# MCU.net
KiCad netlist of a schematic drawn in Altium Designer
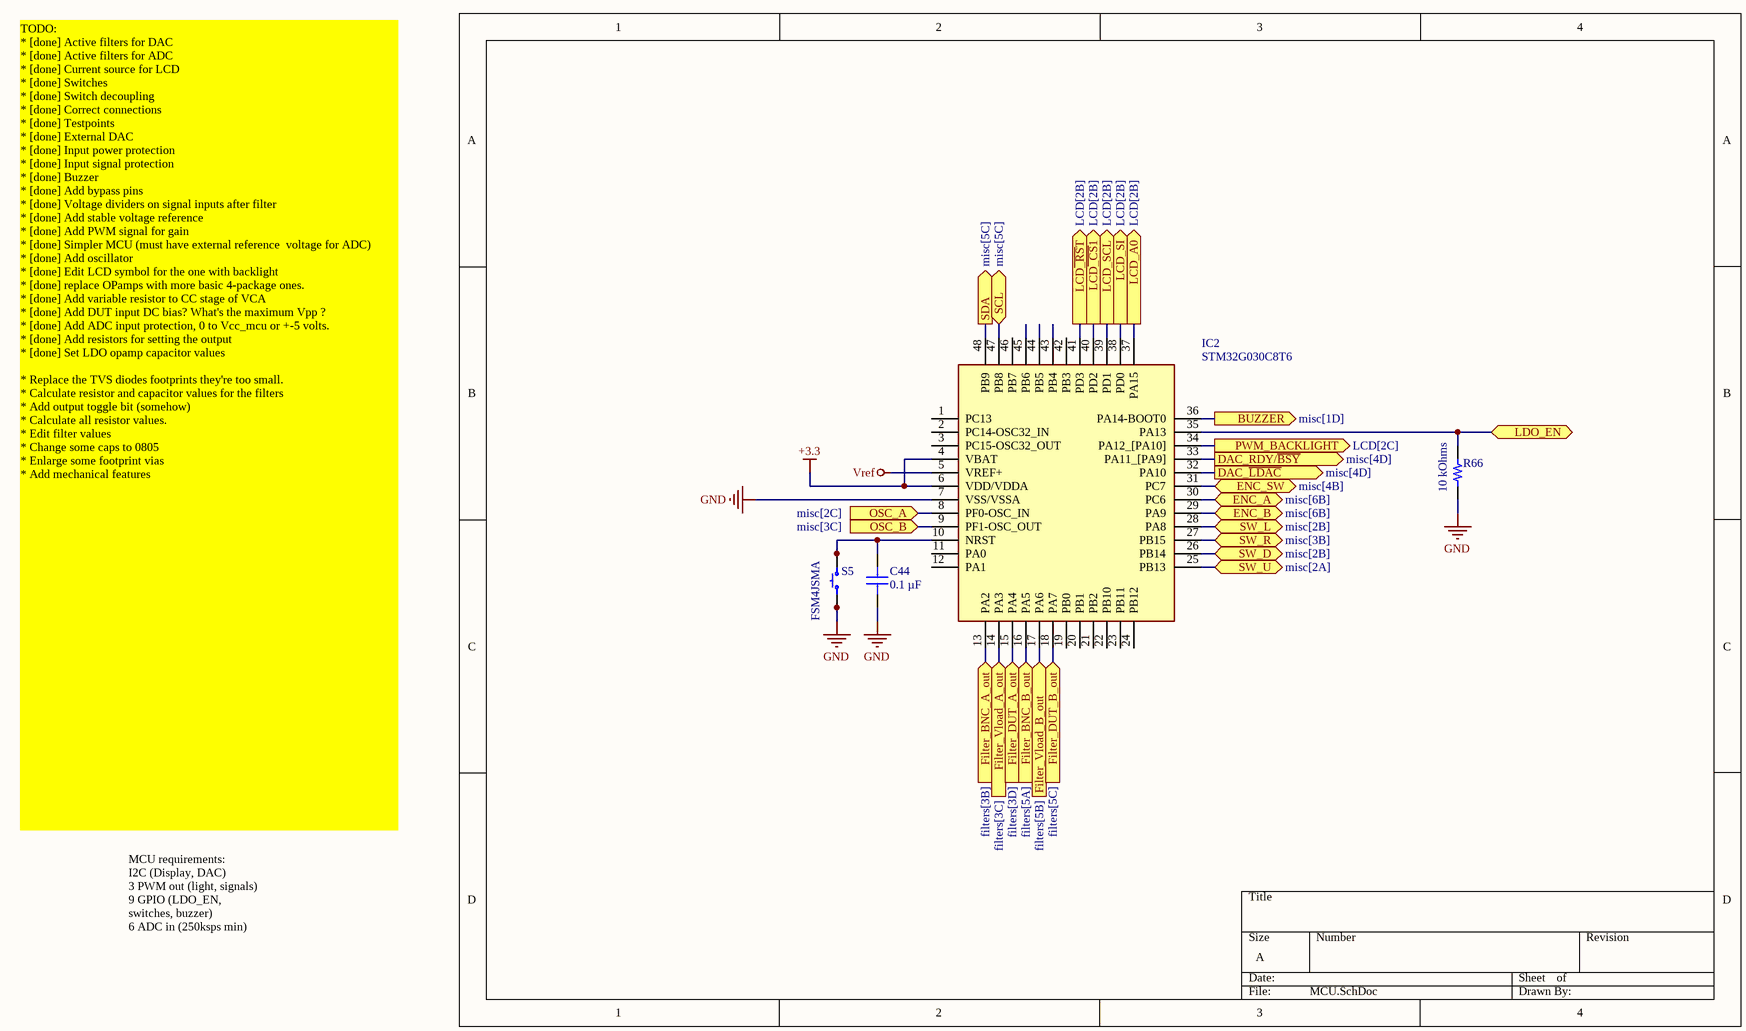
[diagram p0: MCU.SchDoc]

(export (version "E")
  (design (tool "Eeschema 10.0.6"))
  (components
    (comp (ref "C44")
      (value "0.1 µF")
      (footprint "CAP 1206_3216 - 0.8MM")
      (description "CAP CER 0.1UF 50V X7R 1206")
      (fields
        (field (name "PART NUMBER") "885012208087")
        (field (name "CAPACITANCE") "0.1 µF")
        (field (name "MANUFACTURER") "Würth Elektronik")
      )
      (libsource (lib "Celestial Altium Library - altium_library") (part "Capacitor"))
    )
    (comp (ref "IC2")
      (value "STM32G030C8T6")
      (footprint "QFP50P900X900X160-48N")
      (description "Integrated Circuit")
      (fields (field (name "MOUSER PART NUMBER") "511-STM32G030C8T6"))
      (libsource (lib "za_koncar") (part "STM32G030C8T6"))
    )
    (comp (ref "R66")
      (value "10 kOhms")
      (footprint "YAGEO RES 1206_3216")
      (description "RES SMD 10K OHM 1% 1/4W 1206")
      (fields (field (name "PART NUMBER") "RT1206FRE0710KL") (field (name "MANUFACTURER") "Yageo"))
      (libsource (lib "Celestial Altium Library - altium_library") (part "Resistor"))
    )
    (comp (ref "S5")
      (value "FSM4JSMA")
      (footprint "TE FSM4JSMA")
      (description "SWITCH TACTILE SPST-NO 0.05A 24V")
      (fields (field (name "MANUFACTURER") "TE Connectivity ALCOSWITCH Switches"))
      (libsource (lib "Celestial Altium Library - altium_library") (part "SPST-NO 4 PIN"))
    )
  )
  (nets
    (net (code "1") (name "+3.3") (class "Default")
      (node (ref "IC2") (pin "4") (pinfunction "VBAT_4") (pintype "passive"))
      (node (ref "IC2") (pin "6") (pinfunction "VDD/VDDA_6") (pintype "passive"))
    )
    (net (code "2") (name "/BUZZER") (class "Default")
      (node (ref "IC2") (pin "36") (pinfunction "PA14-BOOT0_36") (pintype "passive"))
    )
    (net (code "3") (name "/DAC_RDY{slash}~{BSY}") (class "Default")
      (node (ref "IC2") (pin "33") (pinfunction "PA11_[PA9]_33") (pintype "passive"))
    )
    (net (code "4") (name "/DAC_~{LDAC}") (class "Default")
      (node (ref "IC2") (pin "32") (pinfunction "PA10_32") (pintype "passive"))
    )
    (net (code "5") (name "/ENC_A") (class "Default")
      (node (ref "IC2") (pin "30") (pinfunction "PC6_30") (pintype "passive"))
    )
    (net (code "6") (name "/ENC_B") (class "Default")
      (node (ref "IC2") (pin "29") (pinfunction "PA9_29") (pintype "passive"))
    )
    (net (code "7") (name "/ENC_SW") (class "Default")
      (node (ref "IC2") (pin "31") (pinfunction "PC7_31") (pintype "passive"))
    )
    (net (code "8") (name "/Filter_BNC_A_out") (class "Default")
      (node (ref "IC2") (pin "13") (pinfunction "PA2_13") (pintype "passive"))
    )
    (net (code "9") (name "/Filter_BNC_B_out") (class "Default")
      (node (ref "IC2") (pin "16") (pinfunction "PA5_16") (pintype "passive"))
    )
    (net (code "10") (name "/Filter_DUT_A_out") (class "Default")
      (node (ref "IC2") (pin "15") (pinfunction "PA4_15") (pintype "passive"))
    )
    (net (code "11") (name "/Filter_DUT_B_out") (class "Default")
      (node (ref "IC2") (pin "18") (pinfunction "PA7_18") (pintype "passive"))
    )
    (net (code "12") (name "/Filter_Vload_A_out") (class "Default")
      (node (ref "IC2") (pin "14") (pinfunction "PA3_14") (pintype "passive"))
    )
    (net (code "13") (name "/Filter_Vload_B_out") (class "Default")
      (node (ref "IC2") (pin "17") (pinfunction "PA6_17") (pintype "passive"))
    )
    (net (code "14") (name "/LCD_A0") (class "Default")
      (node (ref "IC2") (pin "37") (pinfunction "PA15_37") (pintype "passive"))
    )
    (net (code "15") (name "/LCD_SCL") (class "Default")
      (node (ref "IC2") (pin "39") (pinfunction "PD1_39") (pintype "passive"))
    )
    (net (code "16") (name "/LCD_SI") (class "Default")
      (node (ref "IC2") (pin "38") (pinfunction "PD0_38") (pintype "passive"))
    )
    (net (code "17") (name "/LCD~{_CS}1") (class "Default")
      (node (ref "IC2") (pin "40") (pinfunction "PD2_40") (pintype "passive"))
    )
    (net (code "18") (name "/LCD~{_RS}T") (class "Default")
      (node (ref "IC2") (pin "41") (pinfunction "PD3_41") (pintype "passive"))
    )
    (net (code "19") (name "/LDO_EN") (class "Default")
      (node (ref "IC2") (pin "35") (pinfunction "PA13_35") (pintype "passive"))
      (node (ref "R66") (pin "1") (pinfunction "1_1") (pintype "passive"))
    )
    (net (code "20") (name "/OSC_A") (class "Default")
      (node (ref "IC2") (pin "8") (pinfunction "PF0-OSC_IN_8") (pintype "passive"))
    )
    (net (code "21") (name "/OSC_B") (class "Default")
      (node (ref "IC2") (pin "9") (pinfunction "PF1-OSC_OUT_9") (pintype "passive"))
    )
    (net (code "22") (name "/PWM_BACKLIGHT") (class "Default")
      (node (ref "IC2") (pin "34") (pinfunction "PA12_[PA10]_34") (pintype "passive"))
    )
    (net (code "23") (name "/SCL") (class "Default")
      (node (ref "IC2") (pin "47") (pinfunction "PB8_47") (pintype "passive"))
    )
    (net (code "24") (name "/SDA") (class "Default")
      (node (ref "IC2") (pin "48") (pinfunction "PB9_48") (pintype "passive"))
    )
    (net (code "25") (name "/SW_D") (class "Default")
      (node (ref "IC2") (pin "26") (pinfunction "PB14_26") (pintype "passive"))
    )
    (net (code "26") (name "/SW_L") (class "Default")
      (node (ref "IC2") (pin "28") (pinfunction "PA8_28") (pintype "passive"))
    )
    (net (code "27") (name "/SW_R") (class "Default")
      (node (ref "IC2") (pin "27") (pinfunction "PB15_27") (pintype "passive"))
    )
    (net (code "28") (name "/SW_U") (class "Default")
      (node (ref "IC2") (pin "25") (pinfunction "PB13_25") (pintype "passive"))
    )
    (net (code "29") (name "GND") (class "Default")
      (node (ref "C44") (pin "1") (pinfunction "1_1") (pintype "passive"))
      (node (ref "IC2") (pin "7") (pinfunction "VSS/VSSA_7") (pintype "passive"))
      (node (ref "R66") (pin "2") (pinfunction "2_2") (pintype "passive"))
      (node (ref "S5") (pin "1") (pinfunction "1_1") (pintype "passive"))
      (node (ref "S5") (pin "2") (pinfunction "2_2") (pintype "passive"))
    )
    (net (code "30") (name "Net-(IC2-NRST)") (class "Default")
      (node (ref "C44") (pin "2") (pinfunction "2_2") (pintype "passive"))
      (node (ref "IC2") (pin "10") (pinfunction "NRST_10") (pintype "passive"))
      (node (ref "S5") (pin "3") (pinfunction "3_3") (pintype "passive"))
      (node (ref "S5") (pin "4") (pinfunction "4_4") (pintype "passive"))
    )
    (net (code "31") (name "Vref") (class "Default")
      (node (ref "IC2") (pin "5") (pinfunction "VREF+_5") (pintype "passive"))
    )
    (net (code "32") (name "unconnected-(IC2-PA0-Pad11)") (class "Default")
      (node (ref "IC2") (pin "11") (pinfunction "PA0_11") (pintype "passive"))
    )
    (net (code "33") (name "unconnected-(IC2-PA1-Pad12)") (class "Default")
      (node (ref "IC2") (pin "12") (pinfunction "PA1_12") (pintype "passive"))
    )
    (net (code "34") (name "unconnected-(IC2-PB0-Pad19)") (class "Default")
      (node (ref "IC2") (pin "19") (pinfunction "PB0_19") (pintype "passive"))
    )
    (net (code "35") (name "unconnected-(IC2-PB1-Pad20)") (class "Default")
      (node (ref "IC2") (pin "20") (pinfunction "PB1_20") (pintype "passive"))
    )
    (net (code "36") (name "unconnected-(IC2-PB2-Pad21)") (class "Default")
      (node (ref "IC2") (pin "21") (pinfunction "PB2_21") (pintype "passive"))
    )
    (net (code "37") (name "unconnected-(IC2-PB3-Pad42)") (class "Default")
      (node (ref "IC2") (pin "42") (pinfunction "PB3_42") (pintype "passive"))
    )
    (net (code "38") (name "unconnected-(IC2-PB4-Pad43)") (class "Default")
      (node (ref "IC2") (pin "43") (pinfunction "PB4_43") (pintype "passive"))
    )
    (net (code "39") (name "unconnected-(IC2-PB5-Pad44)") (class "Default")
      (node (ref "IC2") (pin "44") (pinfunction "PB5_44") (pintype "passive"))
    )
    (net (code "40") (name "unconnected-(IC2-PB6-Pad45)") (class "Default")
      (node (ref "IC2") (pin "45") (pinfunction "PB6_45") (pintype "passive"))
    )
    (net (code "41") (name "unconnected-(IC2-PB7-Pad46)") (class "Default")
      (node (ref "IC2") (pin "46") (pinfunction "PB7_46") (pintype "passive"))
    )
    (net (code "42") (name "unconnected-(IC2-PB10-Pad22)") (class "Default")
      (node (ref "IC2") (pin "22") (pinfunction "PB10_22") (pintype "passive"))
    )
    (net (code "43") (name "unconnected-(IC2-PB11-Pad23)") (class "Default")
      (node (ref "IC2") (pin "23") (pinfunction "PB11_23") (pintype "passive"))
    )
    (net (code "44") (name "unconnected-(IC2-PB12-Pad24)") (class "Default")
      (node (ref "IC2") (pin "24") (pinfunction "PB12_24") (pintype "passive"))
    )
    (net (code "45") (name "unconnected-(IC2-PC13-Pad1)") (class "Default")
      (node (ref "IC2") (pin "1") (pinfunction "PC13_1") (pintype "passive"))
    )
    (net (code "46") (name "unconnected-(IC2-PC14-OSC32_IN-Pad2)") (class "Default")
      (node (ref "IC2") (pin "2") (pinfunction "PC14-OSC32_IN_2") (pintype "passive"))
    )
    (net (code "47") (name "unconnected-(IC2-PC15-OSC32_OUT-Pad3)") (class "Default")
      (node (ref "IC2") (pin "3") (pinfunction "PC15-OSC32_OUT_3") (pintype "passive"))
    )
  )
)
